# QCopterRC_LED_Sch.net
KiCad netlist of a schematic drawn in Altium Designer
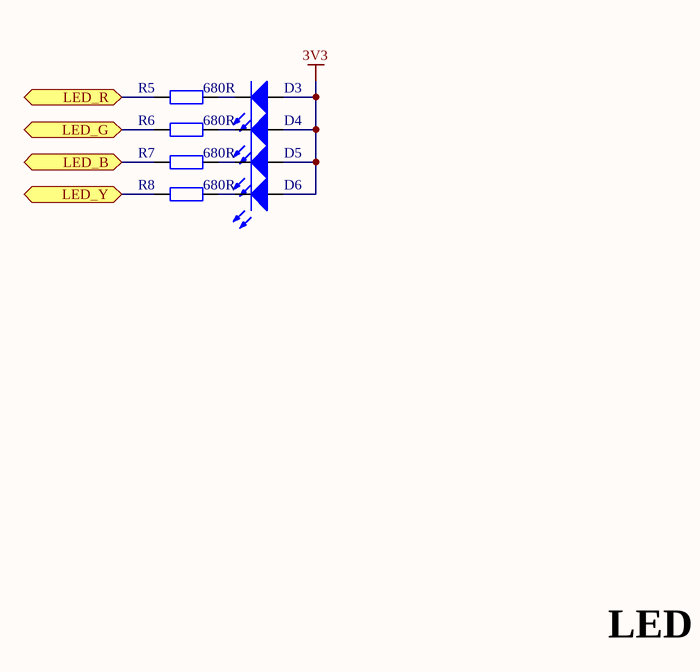
[diagram p0: QCopterRC_LED_Sch.SchDoc]

(export (version "E")
  (design (tool "Eeschema 10.0.6"))
  (components
    (comp (ref "D3")
      (value "LED_0603_RED")
      (footprint "PCB_Active:LED_0603_RED")
      (description "LED")
      (libsource (lib "SCH_Active") (part "LED_0603_RED"))
    )
    (comp (ref "D4")
      (value "LED_0603_GREEN")
      (footprint "PCB_Active:LED_0603_GREEN")
      (description "LED")
      (libsource (lib "SCH_Active") (part "LED_0603_GREEN"))
    )
    (comp (ref "D5")
      (value "LED_0603_BLUE")
      (footprint "PCB_Active:LED_0603_BLUE")
      (description "LED")
      (libsource (lib "SCH_Active") (part "LED_0603_BLUE"))
    )
    (comp (ref "D6")
      (value "LED_0603_YELLOW")
      (footprint "PCB_Active:LED_0603_YELLOW")
      (description "LED")
      (libsource (lib "SCH_Active") (part "LED_0603_YELLOW"))
    )
    (comp (ref "R5")
      (value "680R")
      (footprint "PCB_Passive:RES_0603")
      (description "Resistor")
      (fields (field (name "Comment") "Res_0603"))
      (libsource (lib "SCH_Passive") (part "Res_0603"))
    )
    (comp (ref "R6")
      (value "680R")
      (footprint "PCB_Passive:RES_0603")
      (description "Resistor")
      (fields (field (name "Comment") "Res_0603"))
      (libsource (lib "SCH_Passive") (part "Res_0603"))
    )
    (comp (ref "R7")
      (value "680R")
      (footprint "PCB_Passive:RES_0603")
      (description "Resistor")
      (fields (field (name "Comment") "Res_0603"))
      (libsource (lib "SCH_Passive") (part "Res_0603"))
    )
    (comp (ref "R8")
      (value "680R")
      (footprint "PCB_Passive:RES_0603")
      (description "Resistor")
      (fields (field (name "Comment") "Res_0603"))
      (libsource (lib "SCH_Passive") (part "Res_0603"))
    )
  )
  (nets
    (net (code "1") (name "/LED_B") (class "Default")
      (node (ref "R7") (pin "1") (pinfunction "1_1") (pintype "passive"))
    )
    (net (code "2") (name "/LED_G") (class "Default")
      (node (ref "R6") (pin "1") (pinfunction "1_1") (pintype "passive"))
    )
    (net (code "3") (name "/LED_R") (class "Default")
      (node (ref "R5") (pin "1") (pinfunction "1_1") (pintype "passive"))
    )
    (net (code "4") (name "/LED_Y") (class "Default")
      (node (ref "R8") (pin "1") (pinfunction "1_1") (pintype "passive"))
    )
    (net (code "5") (name "3V3") (class "Default")
      (node (ref "D3") (pin "1") (pinfunction "A_1") (pintype "passive"))
      (node (ref "D4") (pin "1") (pinfunction "A_1") (pintype "passive"))
      (node (ref "D5") (pin "1") (pinfunction "A_1") (pintype "passive"))
      (node (ref "D6") (pin "1") (pinfunction "A_1") (pintype "passive"))
    )
    (net (code "6") (name "Net-(D3-K)") (class "Default")
      (node (ref "D3") (pin "2") (pinfunction "K_2") (pintype "passive"))
      (node (ref "R5") (pin "2") (pinfunction "2_2") (pintype "passive"))
    )
    (net (code "7") (name "Net-(D4-K)") (class "Default")
      (node (ref "D4") (pin "2") (pinfunction "K_2") (pintype "passive"))
      (node (ref "R6") (pin "2") (pinfunction "2_2") (pintype "passive"))
    )
    (net (code "8") (name "Net-(D5-K)") (class "Default")
      (node (ref "D5") (pin "2") (pinfunction "K_2") (pintype "passive"))
      (node (ref "R7") (pin "2") (pinfunction "2_2") (pintype "passive"))
    )
    (net (code "9") (name "Net-(D6-K)") (class "Default")
      (node (ref "D6") (pin "2") (pinfunction "K_2") (pintype "passive"))
      (node (ref "R8") (pin "2") (pinfunction "2_2") (pintype "passive"))
    )
  )
)
